# LSE_Piezo_Driver.net
KiCad netlist of a schematic drawn in Altium Designer
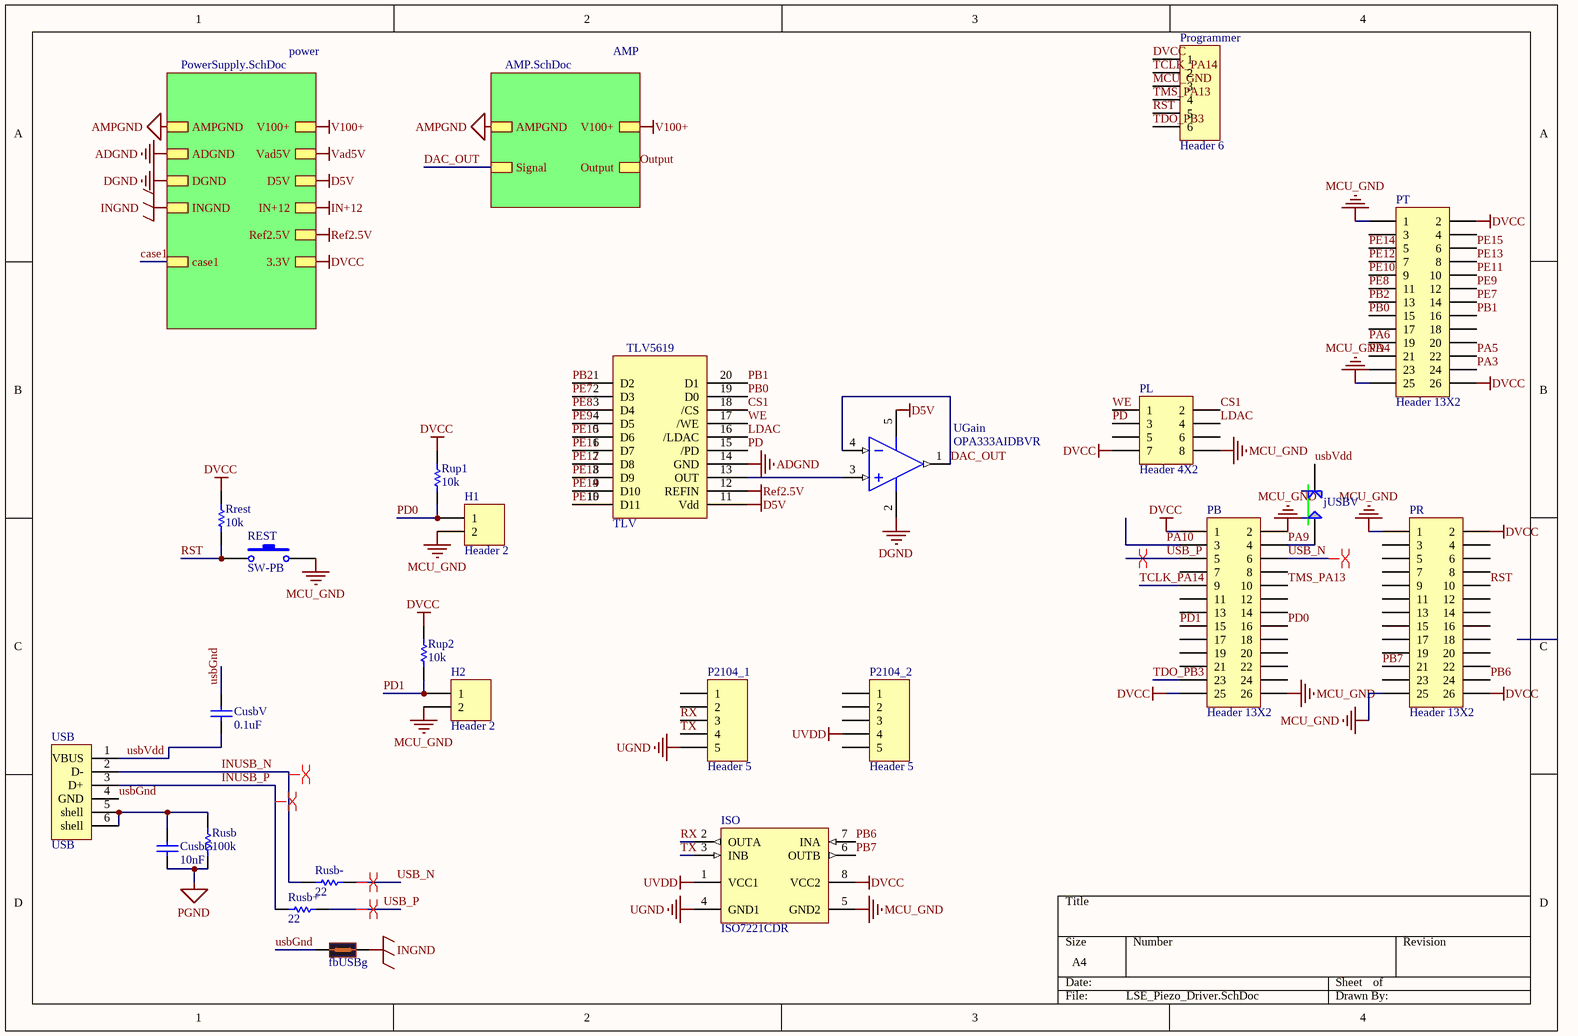
[diagram p0: LSE_Piezo_Driver.SchDoc]

(export (version "E")
  (design (tool "Eeschema 10.0.6"))
  (components
    (comp (ref "CusbG")
      (value "10nF")
      (footprint "C_0603")
      (description "Capacitor (Semiconductor SIM Model)")
      (fields (field (name "PARTNO") "?"))
      (libsource (lib "Lib_AMNL") (part "Csemi"))
    )
    (comp (ref "CusbV")
      (value "0.1uF")
      (footprint "C_0603")
      (description "Capacitor (Semiconductor SIM Model)")
      (fields (field (name "PARTNO") "?"))
      (libsource (lib "Lib_AMNL") (part "Csemi"))
    )
    (comp (ref "fbUSBg")
      (value "MH2029-300YCT-ND")
      (footprint "FB_0805")
      (description "Ferrite bead")
      (libsource (lib "Lib_AMNL") (part "FerriteBead"))
    )
    (comp (ref "H1")
      (value "Header 2")
      (footprint "HDR1X2")
      (description "Header, 2-Pin")
      (fields (field (name "PUBLISHER") "Altium Limited"))
      (libsource (lib "Miscellaneous Connectors") (part "Header 2"))
    )
    (comp (ref "H2")
      (value "Header 2")
      (footprint "HDR1X2")
      (description "Header, 2-Pin")
      (fields (field (name "PUBLISHER") "Altium Limited"))
      (libsource (lib "Miscellaneous Connectors") (part "Header 2"))
    )
    (comp (ref "ISO")
      (value "ISO7221CDR")
      (footprint "D0008A_N")
      (fields (field (name "MANUFACTURER") "Texas Instruments"))
      (libsource (lib "TI Interface Isolator") (part "ISO7221CDR"))
    )
    (comp (ref "jUSBV")
      (value "Jumper")
      (footprint "HDR1X2")
      (description "solderable jumper")
      (libsource (lib "Lib_AMNL") (part "Jumper"))
    )
    (comp (ref "P2104_1")
      (value "Header 5")
      (footprint "HDR1X5")
      (description "Header, 5-Pin")
      (fields (field (name "PUBLISHER") "Altium Limited"))
      (libsource (lib "Miscellaneous Connectors") (part "Header 5"))
    )
    (comp (ref "P2104_2")
      (value "Header 5")
      (footprint "HDR1X5")
      (description "Header, 5-Pin")
      (fields (field (name "PUBLISHER") "Altium Limited"))
      (libsource (lib "Miscellaneous Connectors") (part "Header 5"))
    )
    (comp (ref "PB")
      (value "Header 13X2")
      (footprint "HDR2X13")
      (description "Header, 13-Pin, Dual row")
      (fields (field (name "PUBLISHER") "Altium Limited"))
      (libsource (lib "Miscellaneous Connectors") (part "Header 13X2"))
    )
    (comp (ref "PL")
      (value "Header 4X2")
      (footprint "HDR2X4")
      (description "Header, 4-Pin, Dual row")
      (fields (field (name "PUBLISHER") "Altium Limited"))
      (libsource (lib "Miscellaneous Connectors") (part "Header 4X2"))
    )
    (comp (ref "PR")
      (value "Header 13X2")
      (footprint "HDR2X13")
      (description "Header, 13-Pin, Dual row")
      (fields (field (name "PUBLISHER") "Altium Limited"))
      (libsource (lib "Miscellaneous Connectors") (part "Header 13X2"))
    )
    (comp (ref "Programmer")
      (value "Header 6")
      (footprint "HDR1X6")
      (description "Header, 6-Pin")
      (fields (field (name "PUBLISHER") "Altium Limited"))
      (libsource (lib "Miscellaneous Connectors") (part "Header 6"))
    )
    (comp (ref "PT")
      (value "Header 13X2")
      (footprint "HDR2X13")
      (description "Header, 13-Pin, Dual row")
      (fields (field (name "PUBLISHER") "Altium Limited"))
      (libsource (lib "Miscellaneous Connectors") (part "Header 13X2"))
    )
    (comp (ref "REST")
      (value "SW-PB")
      (footprint "SPST-2")
      (description "Switch")
      (fields (field (name "PUBLISHER") "Altium Limited"))
      (libsource (lib "Miscellaneous Devices") (part "SW-PB"))
    )
    (comp (ref "Rrest")
      (value "10k")
      (footprint "0603")
      (description "Semiconductor Resistor, SMD")
      (fields (field (name "PARTNO") "?"))
      (libsource (lib "Lib_AMNL") (part "Rsemi"))
    )
    (comp (ref "Rup1")
      (value "10k")
      (footprint "0603")
      (description "Semiconductor Resistor, SMD")
      (fields (field (name "PARTNO") "?"))
      (libsource (lib "Lib_AMNL") (part "Rsemi"))
    )
    (comp (ref "Rup2")
      (value "10k")
      (footprint "0603")
      (description "Semiconductor Resistor, SMD")
      (fields (field (name "PARTNO") "?"))
      (libsource (lib "Lib_AMNL") (part "Rsemi"))
    )
    (comp (ref "Rusb")
      (value "100k")
      (footprint "0603")
      (description "Semiconductor Resistor, SMD")
      (fields (field (name "PARTNO") "?"))
      (libsource (lib "Lib_AMNL") (part "Rsemi"))
    )
    (comp (ref "Rusb+")
      (value "22")
      (footprint "0603")
      (description "Semiconductor Resistor, SMD")
      (fields (field (name "PARTNO") "?"))
      (libsource (lib "Lib_AMNL") (part "Rsemi"))
    )
    (comp (ref "Rusb-")
      (value "22")
      (footprint "0603")
      (description "Semiconductor Resistor, SMD")
      (fields (field (name "PARTNO") "?"))
      (libsource (lib "Lib_AMNL") (part "Rsemi"))
    )
    (comp (ref "TLV") (value "TLV5619") (footprint "DW020_L") (libsource (lib "atmel") (part "TLV5619")))
    (comp (ref "UGain")
      (value "OPA333AIDBVR")
      (footprint "TI-DBV5_N")
      (fields (field (name "MANUFACTURER") "Texas Instruments"))
      (libsource (lib "TI Amplifiers and Linear Operational Amplifier Precision Amplifier Part One") (part "OPA333AIDBVR"))
    )
    (comp (ref "USB") (value "USB") (footprint "USB-B") (libsource (lib "USB_PCB") (part "USB")))
  )
  (nets
    (net (code "1") (name "/CS1") (class "Default")
      (node (ref "PL") (pin "2") (pinfunction "2_2") (pintype "passive"))
      (node (ref "TLV") (pin "18") (pinfunction "/CS_18") (pintype "passive"))
    )
    (net (code "2") (name "/DAC_OUT") (class "Default")
      (node (ref "UGain") (pin "1") (pinfunction "OUT_1") (pintype "output"))
      (node (ref "UGain") (pin "4") (pinfunction "IN-_4") (pintype "input"))
    )
    (net (code "3") (name "/INUSB_N") (class "Default")
      (node (ref "Rusb-") (pin "1") (pinfunction "1_1") (pintype "passive"))
      (node (ref "USB") (pin "2") (pinfunction "D-_2") (pintype "passive"))
    )
    (net (code "4") (name "/INUSB_P") (class "Default")
      (node (ref "Rusb+") (pin "1") (pinfunction "1_1") (pintype "passive"))
      (node (ref "USB") (pin "3") (pinfunction "D+_3") (pintype "passive"))
    )
    (net (code "5") (name "/LDAC") (class "Default")
      (node (ref "PL") (pin "4") (pinfunction "4_4") (pintype "passive"))
      (node (ref "TLV") (pin "16") (pinfunction "/LDAC_16") (pintype "passive"))
    )
    (net (code "7") (name "/PA3") (class "Default")
      (node (ref "PT") (pin "24") (pinfunction "24_24") (pintype "passive"))
    )
    (net (code "8") (name "/PA4") (class "Default")
      (node (ref "PT") (pin "21") (pinfunction "21_21") (pintype "passive"))
    )
    (net (code "9") (name "/PA5") (class "Default")
      (node (ref "PT") (pin "22") (pinfunction "22_22") (pintype "passive"))
    )
    (net (code "10") (name "/PA6") (class "Default")
      (node (ref "PT") (pin "19") (pinfunction "19_19") (pintype "passive"))
    )
    (net (code "11") (name "/PA9") (class "Default")
      (node (ref "PB") (pin "4") (pinfunction "4_4") (pintype "passive"))
      (node (ref "jUSBV") (pin "1") (pinfunction "1_1") (pintype "passive"))
    )
    (net (code "12") (name "/PA10") (class "Default")
      (node (ref "PB") (pin "3") (pinfunction "3_3") (pintype "passive"))
    )
    (net (code "13") (name "/PB0") (class "Default")
      (node (ref "PT") (pin "15") (pinfunction "15_15") (pintype "passive"))
      (node (ref "TLV") (pin "19") (pinfunction "D0_19") (pintype "passive"))
    )
    (net (code "14") (name "/PB1") (class "Default")
      (node (ref "PT") (pin "16") (pinfunction "16_16") (pintype "passive"))
      (node (ref "TLV") (pin "20") (pinfunction "D1_20") (pintype "passive"))
    )
    (net (code "15") (name "/PB2") (class "Default")
      (node (ref "PT") (pin "13") (pinfunction "13_13") (pintype "passive"))
      (node (ref "TLV") (pin "1") (pinfunction "D2_1") (pintype "passive"))
    )
    (net (code "16") (name "/PB6") (class "Default")
      (node (ref "ISO") (pin "7") (pinfunction "INA_7") (pintype "input"))
      (node (ref "PR") (pin "24") (pinfunction "24_24") (pintype "passive"))
    )
    (net (code "17") (name "/PB7") (class "Default")
      (node (ref "ISO") (pin "6") (pinfunction "OUTB_6") (pintype "output"))
      (node (ref "PR") (pin "21") (pinfunction "21_21") (pintype "passive"))
    )
    (net (code "18") (name "/PD") (class "Default")
      (node (ref "PL") (pin "3") (pinfunction "3_3") (pintype "passive"))
      (node (ref "TLV") (pin "15") (pinfunction "/PD_15") (pintype "passive"))
    )
    (net (code "19") (name "/PD0") (class "Default")
      (node (ref "H1") (pin "1") (pinfunction "1_1") (pintype "passive"))
      (node (ref "PB") (pin "16") (pinfunction "16_16") (pintype "passive"))
      (node (ref "Rup1") (pin "1") (pinfunction "1_1") (pintype "passive"))
    )
    (net (code "20") (name "/PD1") (class "Default")
      (node (ref "H2") (pin "1") (pinfunction "1_1") (pintype "passive"))
      (node (ref "PB") (pin "15") (pinfunction "15_15") (pintype "passive"))
      (node (ref "Rup2") (pin "1") (pinfunction "1_1") (pintype "passive"))
    )
    (net (code "21") (name "/PE7") (class "Default")
      (node (ref "PT") (pin "14") (pinfunction "14_14") (pintype "passive"))
      (node (ref "TLV") (pin "2") (pinfunction "D3_2") (pintype "passive"))
    )
    (net (code "22") (name "/PE8") (class "Default")
      (node (ref "PT") (pin "11") (pinfunction "11_11") (pintype "passive"))
      (node (ref "TLV") (pin "3") (pinfunction "D4_3") (pintype "passive"))
    )
    (net (code "23") (name "/PE9") (class "Default")
      (node (ref "PT") (pin "12") (pinfunction "12_12") (pintype "passive"))
      (node (ref "TLV") (pin "4") (pinfunction "D5_4") (pintype "passive"))
    )
    (net (code "24") (name "/PE10") (class "Default")
      (node (ref "PT") (pin "9") (pinfunction "9_9") (pintype "passive"))
      (node (ref "TLV") (pin "5") (pinfunction "D6_5") (pintype "passive"))
    )
    (net (code "25") (name "/PE11") (class "Default")
      (node (ref "PT") (pin "10") (pinfunction "10_10") (pintype "passive"))
      (node (ref "TLV") (pin "6") (pinfunction "D7_6") (pintype "passive"))
    )
    (net (code "26") (name "/PE12") (class "Default")
      (node (ref "PT") (pin "7") (pinfunction "7_7") (pintype "passive"))
      (node (ref "TLV") (pin "7") (pinfunction "D8_7") (pintype "passive"))
    )
    (net (code "27") (name "/PE13") (class "Default")
      (node (ref "PT") (pin "8") (pinfunction "8_8") (pintype "passive"))
      (node (ref "TLV") (pin "8") (pinfunction "D9_8") (pintype "passive"))
    )
    (net (code "28") (name "/PE14") (class "Default")
      (node (ref "PT") (pin "5") (pinfunction "5_5") (pintype "passive"))
      (node (ref "TLV") (pin "9") (pinfunction "D10_9") (pintype "passive"))
    )
    (net (code "29") (name "/PE15") (class "Default")
      (node (ref "PT") (pin "6") (pinfunction "6_6") (pintype "passive"))
      (node (ref "TLV") (pin "10") (pinfunction "D11_10") (pintype "passive"))
    )
    (net (code "30") (name "/RST") (class "Default")
      (node (ref "PR") (pin "10") (pinfunction "10_10") (pintype "passive"))
      (node (ref "Programmer") (pin "5") (pinfunction "5_5") (pintype "passive"))
      (node (ref "REST") (pin "1") (pinfunction "1_1") (pintype "passive"))
      (node (ref "Rrest") (pin "1") (pinfunction "1_1") (pintype "passive"))
    )
    (net (code "31") (name "/RX") (class "Default")
      (node (ref "ISO") (pin "2") (pinfunction "OUTA_2") (pintype "output"))
      (node (ref "P2104_1") (pin "3") (pinfunction "3_3") (pintype "passive"))
    )
    (net (code "32") (name "/TCLK_PA14") (class "Default")
      (node (ref "PB") (pin "9") (pinfunction "9_9") (pintype "passive"))
      (node (ref "Programmer") (pin "2") (pinfunction "2_2") (pintype "passive"))
    )
    (net (code "33") (name "/TDO_PB3") (class "Default")
      (node (ref "PB") (pin "23") (pinfunction "23_23") (pintype "passive"))
      (node (ref "Programmer") (pin "6") (pinfunction "6_6") (pintype "passive"))
    )
    (net (code "34") (name "/TMS_PA13") (class "Default")
      (node (ref "PB") (pin "10") (pinfunction "10_10") (pintype "passive"))
      (node (ref "Programmer") (pin "4") (pinfunction "4_4") (pintype "passive"))
    )
    (net (code "35") (name "/TX") (class "Default")
      (node (ref "ISO") (pin "3") (pinfunction "INB_3") (pintype "input"))
      (node (ref "P2104_1") (pin "4") (pinfunction "4_4") (pintype "passive"))
    )
    (net (code "36") (name "/USB_N") (class "Default")
      (node (ref "PB") (pin "6") (pinfunction "6_6") (pintype "passive"))
      (node (ref "Rusb-") (pin "2") (pinfunction "2_2") (pintype "passive"))
    )
    (net (code "37") (name "/USB_P") (class "Default")
      (node (ref "PB") (pin "5") (pinfunction "5_5") (pintype "passive"))
      (node (ref "Rusb+") (pin "2") (pinfunction "2_2") (pintype "passive"))
    )
    (net (code "38") (name "/WE") (class "Default")
      (node (ref "PL") (pin "1") (pinfunction "1_1") (pintype "passive"))
      (node (ref "TLV") (pin "17") (pinfunction "/WE_17") (pintype "passive"))
    )
    (net (code "40") (name "/usbGnd") (class "Default")
      (node (ref "CusbV") (pin "2") (pinfunction "2_2") (pintype "passive"))
      (node (ref "USB") (pin "4") (pinfunction "GND_4") (pintype "passive"))
      (node (ref "fbUSBg") (pin "1") (pinfunction "1_1") (pintype "passive"))
    )
    (net (code "41") (name "/usbVdd") (class "Default")
      (node (ref "CusbV") (pin "1") (pinfunction "1_1") (pintype "passive"))
      (node (ref "USB") (pin "1") (pinfunction "VBUS_1") (pintype "passive"))
      (node (ref "jUSBV") (pin "2") (pinfunction "2_2") (pintype "passive"))
    )
    (net (code "42") (name "ADGND") (class "Default")
      (node (ref "TLV") (pin "14") (pinfunction "GND_14") (pintype "passive"))
    )
    (net (code "44") (name "D5V") (class "Default")
      (node (ref "TLV") (pin "11") (pinfunction "Vdd_11") (pintype "passive"))
      (node (ref "UGain") (pin "5") (pinfunction "V+_5") (pintype "power_in"))
    )
    (net (code "45") (name "DGND") (class "Default")
      (node (ref "UGain") (pin "2") (pinfunction "V-_2") (pintype "power_in"))
    )
    (net (code "46") (name "DVCC") (class "Default")
      (node (ref "ISO") (pin "8") (pinfunction "VCC2_8") (pintype "power_in"))
      (node (ref "PB") (pin "1") (pinfunction "1_1") (pintype "passive"))
      (node (ref "PB") (pin "25") (pinfunction "25_25") (pintype "passive"))
      (node (ref "PL") (pin "7") (pinfunction "7_7") (pintype "passive"))
      (node (ref "PR") (pin "2") (pinfunction "2_2") (pintype "passive"))
      (node (ref "PR") (pin "26") (pinfunction "26_26") (pintype "passive"))
      (node (ref "PT") (pin "2") (pinfunction "2_2") (pintype "passive"))
      (node (ref "PT") (pin "26") (pinfunction "26_26") (pintype "passive"))
      (node (ref "Programmer") (pin "1") (pinfunction "1_1") (pintype "passive"))
      (node (ref "Rrest") (pin "2") (pinfunction "2_2") (pintype "passive"))
      (node (ref "Rup1") (pin "2") (pinfunction "2_2") (pintype "passive"))
      (node (ref "Rup2") (pin "2") (pinfunction "2_2") (pintype "passive"))
    )
    (net (code "48") (name "INGND") (class "Default")
      (node (ref "fbUSBg") (pin "2") (pinfunction "2_2") (pintype "passive"))
    )
    (net (code "49") (name "MCU_GND") (class "Default")
      (node (ref "H1") (pin "2") (pinfunction "2_2") (pintype "passive"))
      (node (ref "H2") (pin "2") (pinfunction "2_2") (pintype "passive"))
      (node (ref "ISO") (pin "5") (pinfunction "GND2_5") (pintype "power_in"))
      (node (ref "PB") (pin "2") (pinfunction "2_2") (pintype "passive"))
      (node (ref "PB") (pin "26") (pinfunction "26_26") (pintype "passive"))
      (node (ref "PL") (pin "8") (pinfunction "8_8") (pintype "passive"))
      (node (ref "PR") (pin "1") (pinfunction "1_1") (pintype "passive"))
      (node (ref "PR") (pin "25") (pinfunction "25_25") (pintype "passive"))
      (node (ref "PT") (pin "1") (pinfunction "1_1") (pintype "passive"))
      (node (ref "PT") (pin "25") (pinfunction "25_25") (pintype "passive"))
      (node (ref "Programmer") (pin "3") (pinfunction "3_3") (pintype "passive"))
      (node (ref "REST") (pin "2") (pinfunction "2_2") (pintype "passive"))
    )
    (net (code "50") (name "Net-(CusbG-Pad2)") (class "Default")
      (node (ref "CusbG") (pin "2") (pinfunction "2_2") (pintype "passive"))
      (node (ref "Rusb") (pin "2") (pinfunction "2_2") (pintype "passive"))
      (node (ref "USB") (pin "5") (pinfunction "shell_5") (pintype "passive"))
      (node (ref "USB") (pin "6") (pinfunction "shell_6") (pintype "passive"))
    )
    (net (code "51") (name "Net-(TLV-OUT)") (class "Default")
      (node (ref "TLV") (pin "13") (pinfunction "OUT_13") (pintype "passive"))
      (node (ref "UGain") (pin "3") (pinfunction "IN+_3") (pintype "input"))
    )
    (net (code "52") (name "PGND") (class "Default")
      (node (ref "CusbG") (pin "1") (pinfunction "1_1") (pintype "passive"))
      (node (ref "Rusb") (pin "1") (pinfunction "1_1") (pintype "passive"))
    )
    (net (code "53") (name "Ref2.5V") (class "Default")
      (node (ref "TLV") (pin "12") (pinfunction "REFIN_12") (pintype "passive"))
    )
    (net (code "54") (name "UGND") (class "Default")
      (node (ref "ISO") (pin "4") (pinfunction "GND1_4") (pintype "power_in"))
      (node (ref "P2104_1") (pin "5") (pinfunction "5_5") (pintype "passive"))
    )
    (net (code "55") (name "UVDD") (class "Default")
      (node (ref "ISO") (pin "1") (pinfunction "VCC1_1") (pintype "power_in"))
      (node (ref "P2104_2") (pin "4") (pinfunction "4_4") (pintype "passive"))
    )
    (net (code "58") (name "unconnected-(P2104_1-Pad1)") (class "Default")
      (node (ref "P2104_1") (pin "1") (pinfunction "1_1") (pintype "passive"))
    )
    (net (code "59") (name "unconnected-(P2104_1-Pad2)") (class "Default")
      (node (ref "P2104_1") (pin "2") (pinfunction "2_2") (pintype "passive"))
    )
    (net (code "60") (name "unconnected-(P2104_2-Pad1)") (class "Default")
      (node (ref "P2104_2") (pin "1") (pinfunction "1_1") (pintype "passive"))
    )
    (net (code "61") (name "unconnected-(P2104_2-Pad2)") (class "Default")
      (node (ref "P2104_2") (pin "2") (pinfunction "2_2") (pintype "passive"))
    )
    (net (code "62") (name "unconnected-(P2104_2-Pad3)") (class "Default")
      (node (ref "P2104_2") (pin "3") (pinfunction "3_3") (pintype "passive"))
    )
    (net (code "63") (name "unconnected-(P2104_2-Pad5)") (class "Default")
      (node (ref "P2104_2") (pin "5") (pinfunction "5_5") (pintype "passive"))
    )
    (net (code "64") (name "unconnected-(PB-Pad7)") (class "Default")
      (node (ref "PB") (pin "7") (pinfunction "7_7") (pintype "passive"))
    )
    (net (code "65") (name "unconnected-(PB-Pad8)") (class "Default")
      (node (ref "PB") (pin "8") (pinfunction "8_8") (pintype "passive"))
    )
    (net (code "66") (name "unconnected-(PB-Pad11)") (class "Default")
      (node (ref "PB") (pin "11") (pinfunction "11_11") (pintype "passive"))
    )
    (net (code "67") (name "unconnected-(PB-Pad12)") (class "Default")
      (node (ref "PB") (pin "12") (pinfunction "12_12") (pintype "passive"))
    )
    (net (code "68") (name "unconnected-(PB-Pad13)") (class "Default")
      (node (ref "PB") (pin "13") (pinfunction "13_13") (pintype "passive"))
    )
    (net (code "69") (name "unconnected-(PB-Pad14)") (class "Default")
      (node (ref "PB") (pin "14") (pinfunction "14_14") (pintype "passive"))
    )
    (net (code "70") (name "unconnected-(PB-Pad17)") (class "Default")
      (node (ref "PB") (pin "17") (pinfunction "17_17") (pintype "passive"))
    )
    (net (code "71") (name "unconnected-(PB-Pad18)") (class "Default")
      (node (ref "PB") (pin "18") (pinfunction "18_18") (pintype "passive"))
    )
    (net (code "72") (name "unconnected-(PB-Pad19)") (class "Default")
      (node (ref "PB") (pin "19") (pinfunction "19_19") (pintype "passive"))
    )
    (net (code "73") (name "unconnected-(PB-Pad20)") (class "Default")
      (node (ref "PB") (pin "20") (pinfunction "20_20") (pintype "passive"))
    )
    (net (code "74") (name "unconnected-(PB-Pad21)") (class "Default")
      (node (ref "PB") (pin "21") (pinfunction "21_21") (pintype "passive"))
    )
    (net (code "75") (name "unconnected-(PB-Pad22)") (class "Default")
      (node (ref "PB") (pin "22") (pinfunction "22_22") (pintype "passive"))
    )
    (net (code "76") (name "unconnected-(PB-Pad24)") (class "Default")
      (node (ref "PB") (pin "24") (pinfunction "24_24") (pintype "passive"))
    )
    (net (code "77") (name "unconnected-(PL-Pad5)") (class "Default")
      (node (ref "PL") (pin "5") (pinfunction "5_5") (pintype "passive"))
    )
    (net (code "78") (name "unconnected-(PL-Pad6)") (class "Default")
      (node (ref "PL") (pin "6") (pinfunction "6_6") (pintype "passive"))
    )
    (net (code "79") (name "unconnected-(PR-Pad3)") (class "Default")
      (node (ref "PR") (pin "3") (pinfunction "3_3") (pintype "passive"))
    )
    (net (code "80") (name "unconnected-(PR-Pad4)") (class "Default")
      (node (ref "PR") (pin "4") (pinfunction "4_4") (pintype "passive"))
    )
    (net (code "81") (name "unconnected-(PR-Pad5)") (class "Default")
      (node (ref "PR") (pin "5") (pinfunction "5_5") (pintype "passive"))
    )
    (net (code "82") (name "unconnected-(PR-Pad6)") (class "Default")
      (node (ref "PR") (pin "6") (pinfunction "6_6") (pintype "passive"))
    )
    (net (code "83") (name "unconnected-(PR-Pad7)") (class "Default")
      (node (ref "PR") (pin "7") (pinfunction "7_7") (pintype "passive"))
    )
    (net (code "84") (name "unconnected-(PR-Pad8)") (class "Default")
      (node (ref "PR") (pin "8") (pinfunction "8_8") (pintype "passive"))
    )
    (net (code "85") (name "unconnected-(PR-Pad9)") (class "Default")
      (node (ref "PR") (pin "9") (pinfunction "9_9") (pintype "passive"))
    )
    (net (code "86") (name "unconnected-(PR-Pad11)") (class "Default")
      (node (ref "PR") (pin "11") (pinfunction "11_11") (pintype "passive"))
    )
    (net (code "87") (name "unconnected-(PR-Pad12)") (class "Default")
      (node (ref "PR") (pin "12") (pinfunction "12_12") (pintype "passive"))
    )
    (net (code "88") (name "unconnected-(PR-Pad13)") (class "Default")
      (node (ref "PR") (pin "13") (pinfunction "13_13") (pintype "passive"))
    )
    (net (code "89") (name "unconnected-(PR-Pad14)") (class "Default")
      (node (ref "PR") (pin "14") (pinfunction "14_14") (pintype "passive"))
    )
    (net (code "90") (name "unconnected-(PR-Pad15)") (class "Default")
      (node (ref "PR") (pin "15") (pinfunction "15_15") (pintype "passive"))
    )
    (net (code "91") (name "unconnected-(PR-Pad16)") (class "Default")
      (node (ref "PR") (pin "16") (pinfunction "16_16") (pintype "passive"))
    )
    (net (code "92") (name "unconnected-(PR-Pad17)") (class "Default")
      (node (ref "PR") (pin "17") (pinfunction "17_17") (pintype "passive"))
    )
    (net (code "93") (name "unconnected-(PR-Pad18)") (class "Default")
      (node (ref "PR") (pin "18") (pinfunction "18_18") (pintype "passive"))
    )
    (net (code "94") (name "unconnected-(PR-Pad19)") (class "Default")
      (node (ref "PR") (pin "19") (pinfunction "19_19") (pintype "passive"))
    )
    (net (code "95") (name "unconnected-(PR-Pad20)") (class "Default")
      (node (ref "PR") (pin "20") (pinfunction "20_20") (pintype "passive"))
    )
    (net (code "96") (name "unconnected-(PR-Pad22)") (class "Default")
      (node (ref "PR") (pin "22") (pinfunction "22_22") (pintype "passive"))
    )
    (net (code "97") (name "unconnected-(PR-Pad23)") (class "Default")
      (node (ref "PR") (pin "23") (pinfunction "23_23") (pintype "passive"))
    )
    (net (code "98") (name "unconnected-(PT-Pad3)") (class "Default")
      (node (ref "PT") (pin "3") (pinfunction "3_3") (pintype "passive"))
    )
    (net (code "99") (name "unconnected-(PT-Pad4)") (class "Default")
      (node (ref "PT") (pin "4") (pinfunction "4_4") (pintype "passive"))
    )
    (net (code "100") (name "unconnected-(PT-Pad17)") (class "Default")
      (node (ref "PT") (pin "17") (pinfunction "17_17") (pintype "passive"))
    )
    (net (code "101") (name "unconnected-(PT-Pad18)") (class "Default")
      (node (ref "PT") (pin "18") (pinfunction "18_18") (pintype "passive"))
    )
    (net (code "102") (name "unconnected-(PT-Pad20)") (class "Default")
      (node (ref "PT") (pin "20") (pinfunction "20_20") (pintype "passive"))
    )
    (net (code "103") (name "unconnected-(PT-Pad23)") (class "Default")
      (node (ref "PT") (pin "23") (pinfunction "23_23") (pintype "passive"))
    )
  )
)
